# ESP_esquem_tico.net
KiCad netlist of a schematic drawn in EAGLE
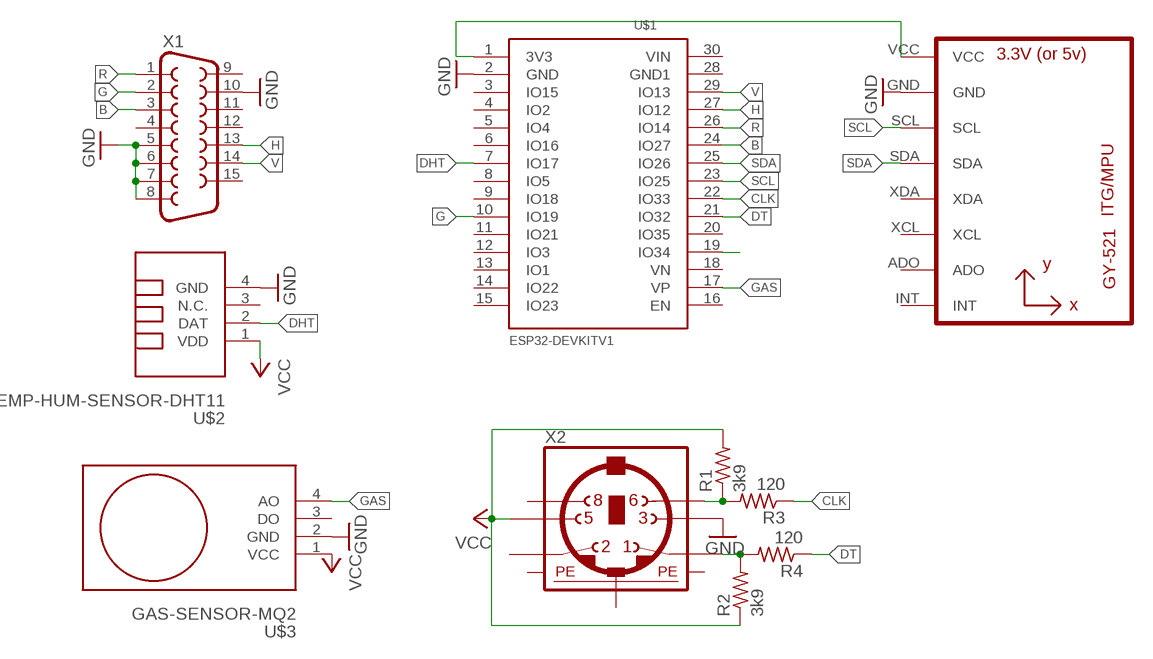
[diagram p0: schematic, sheet 1]

(export (version "E")
  (design (tool "Eeschema 10.0.6"))
  (components
    (comp (ref "R1")
      (value "3k9")
      (footprint "eagle-import:0204_7")
      (libsource (lib "eagle-import") (part "R-US_0204/7"))
    )
    (comp (ref "R2")
      (value "3k9")
      (footprint "eagle-import:0204_7")
      (libsource (lib "eagle-import") (part "R-US_0204/7"))
    )
    (comp (ref "R3")
      (value "120")
      (footprint "eagle-import:0204_7")
      (libsource (lib "eagle-import") (part "R-US_0204/7"))
    )
    (comp (ref "R4")
      (value "120")
      (footprint "eagle-import:0204_7")
      (libsource (lib "eagle-import") (part "R-US_0204/7"))
    )
    (comp (ref "U$1")
      (value "ESP32DEVKITV1")
      (footprint "eagle-import:ESP32-DEVKITV1")
      (libsource (lib "eagle-import") (part "ESP32DEVKITV1"))
    )
    (comp (ref "U$2")
      (value "TEMP-HUM-SENSOR-DHT11")
      (footprint "eagle-import:TEMP-HUM-SENSOR-DHT11")
      (libsource (lib "eagle-import") (part "TEMP-HUM-SENSOR-DHT11"))
    )
    (comp (ref "U$3")
      (value "GAS-SENSOR-MQ2")
      (footprint "eagle-import:GAS-SENSOR-MQ2")
      (libsource (lib "eagle-import") (part "GAS-SENSOR-MQ2"))
    )
    (comp (ref "U1")
      (value "GY-521MPU6050")
      (footprint "eagle-import:GY-521")
      (libsource (lib "eagle-import") (part "GY-521MPU6050"))
    )
    (comp (ref "X1")
      (value "F15HDH")
      (footprint "eagle-import:HDF15H")
      (libsource (lib "eagle-import") (part "F15HDH"))
    )
    (comp (ref "X2")
      (value "MINI_DIN_6")
      (footprint "eagle-import:M_DIN6")
      (libsource (lib "eagle-import") (part "MINI_DIN_6"))
    )
  )
  (nets
    (net (code "1") (name "/PE1") (class "Default")
      (node (ref "X2") (pin "SH1") (pinfunction "PE1_SH1") (pintype "power_in"))
    )
    (net (code "2") (name "/PE2") (class "Default")
      (node (ref "X2") (pin "SH2") (pinfunction "PE2_SH2") (pintype "power_in"))
    )
    (net (code "3") (name "/PE3") (class "Default")
      (node (ref "X2") (pin "SH3") (pinfunction "PE3_SH3") (pintype "power_in"))
    )
    (net (code "4") (name "B") (class "Default")
      (node (ref "U$1") (pin "24") (pinfunction "IO27_24") (pintype "bidirectional"))
      (node (ref "X1") (pin "3") (pinfunction "3_3") (pintype "passive"))
    )
    (net (code "5") (name "CLK") (class "Default")
      (node (ref "R3") (pin "1") (pinfunction "1_1") (pintype "passive"))
      (node (ref "U$1") (pin "22") (pinfunction "IO33_22") (pintype "bidirectional"))
    )
    (net (code "6") (name "DHT") (class "Default")
      (node (ref "U$1") (pin "7") (pinfunction "IO17_7") (pintype "bidirectional"))
      (node (ref "U$2") (pin "2") (pinfunction "DAT_2") (pintype "bidirectional"))
    )
    (net (code "7") (name "DT") (class "Default")
      (node (ref "R4") (pin "1") (pinfunction "1_1") (pintype "passive"))
      (node (ref "U$1") (pin "21") (pinfunction "IO32_21") (pintype "bidirectional"))
    )
    (net (code "8") (name "G") (class "Default")
      (node (ref "U$1") (pin "10") (pinfunction "IO19_10") (pintype "bidirectional"))
      (node (ref "X1") (pin "2") (pinfunction "2_2") (pintype "passive"))
    )
    (net (code "9") (name "GAS") (class "Default")
      (node (ref "U$1") (pin "17") (pinfunction "VP_17") (pintype "bidirectional"))
      (node (ref "U$3") (pin "4") (pinfunction "AO_4") (pintype "output"))
    )
    (net (code "10") (name "GND") (class "Default")
      (node (ref "U$1") (pin "2") (pinfunction "GND_2") (pintype "bidirectional"))
      (node (ref "U$2") (pin "4") (pinfunction "GND_4") (pintype "power_in"))
      (node (ref "U$3") (pin "2") (pinfunction "GND_2") (pintype "power_in"))
      (node (ref "U1") (pin "GND") (pinfunction "GND_GND") (pintype "bidirectional"))
      (node (ref "X1") (pin "10") (pinfunction "10_10") (pintype "passive"))
      (node (ref "X1") (pin "5") (pinfunction "5_5") (pintype "passive"))
      (node (ref "X1") (pin "6") (pinfunction "6_6") (pintype "passive"))
      (node (ref "X1") (pin "7") (pinfunction "7_7") (pintype "passive"))
      (node (ref "X1") (pin "8") (pinfunction "8_8") (pintype "passive"))
      (node (ref "X2") (pin "3") (pinfunction "3_3") (pintype "passive"))
    )
    (net (code "11") (name "H") (class "Default")
      (node (ref "U$1") (pin "27") (pinfunction "IO12_27") (pintype "bidirectional"))
      (node (ref "X1") (pin "13") (pinfunction "13_13") (pintype "passive"))
    )
    (net (code "12") (name "Net-(R1-Pad1)") (class "Default")
      (node (ref "R1") (pin "1") (pinfunction "1_1") (pintype "passive"))
      (node (ref "R3") (pin "2") (pinfunction "2_2") (pintype "passive"))
      (node (ref "X2") (pin "6") (pinfunction "6_6") (pintype "passive"))
    )
    (net (code "13") (name "Net-(R2-Pad2)") (class "Default")
      (node (ref "R2") (pin "2") (pinfunction "2_2") (pintype "passive"))
      (node (ref "R4") (pin "2") (pinfunction "2_2") (pintype "passive"))
      (node (ref "X2") (pin "1") (pinfunction "1_1") (pintype "passive"))
    )
    (net (code "14") (name "Net-(U$1-3V3)") (class "Default")
      (node (ref "U$1") (pin "1") (pinfunction "3V3_1") (pintype "bidirectional"))
      (node (ref "U1") (pin "VCC") (pinfunction "VCC_VCC") (pintype "bidirectional"))
    )
    (net (code "15") (name "R") (class "Default")
      (node (ref "U$1") (pin "26") (pinfunction "IO14_26") (pintype "bidirectional"))
      (node (ref "X1") (pin "1") (pinfunction "1_1") (pintype "passive"))
    )
    (net (code "16") (name "SCL") (class "Default")
      (node (ref "U$1") (pin "23") (pinfunction "IO25_23") (pintype "bidirectional"))
      (node (ref "U1") (pin "SCL") (pinfunction "SCL_SCL") (pintype "bidirectional"))
    )
    (net (code "17") (name "SDA") (class "Default")
      (node (ref "U$1") (pin "25") (pinfunction "IO26_25") (pintype "bidirectional"))
      (node (ref "U1") (pin "SDA") (pinfunction "SDA_SDA") (pintype "bidirectional"))
    )
    (net (code "18") (name "V") (class "Default")
      (node (ref "U$1") (pin "29") (pinfunction "IO13_29") (pintype "bidirectional"))
      (node (ref "X1") (pin "14") (pinfunction "14_14") (pintype "passive"))
    )
    (net (code "19") (name "VCC") (class "Default")
      (node (ref "R1") (pin "2") (pinfunction "2_2") (pintype "passive"))
      (node (ref "R2") (pin "1") (pinfunction "1_1") (pintype "passive"))
      (node (ref "U$2") (pin "1") (pinfunction "VDD_1") (pintype "power_in"))
      (node (ref "U$3") (pin "1") (pinfunction "VCC_1") (pintype "power_in"))
      (node (ref "X2") (pin "5") (pinfunction "5_5") (pintype "passive"))
    )
    (net (code "20") (name "unconnected-(U$1-EN-Pad16)") (class "Default")
      (node (ref "U$1") (pin "16") (pinfunction "EN_16") (pintype "bidirectional"))
    )
    (net (code "21") (name "unconnected-(U$1-GND1-Pad28)") (class "Default")
      (node (ref "U$1") (pin "28") (pinfunction "GND1_28") (pintype "bidirectional"))
    )
    (net (code "22") (name "unconnected-(U$1-IO1-Pad13)") (class "Default")
      (node (ref "U$1") (pin "13") (pinfunction "IO1_13") (pintype "bidirectional"))
    )
    (net (code "23") (name "unconnected-(U$1-IO2-Pad4)") (class "Default")
      (node (ref "U$1") (pin "4") (pinfunction "IO2_4") (pintype "bidirectional"))
    )
    (net (code "24") (name "unconnected-(U$1-IO3-Pad12)") (class "Default")
      (node (ref "U$1") (pin "12") (pinfunction "IO3_12") (pintype "bidirectional"))
    )
    (net (code "25") (name "unconnected-(U$1-IO4-Pad5)") (class "Default")
      (node (ref "U$1") (pin "5") (pinfunction "IO4_5") (pintype "bidirectional"))
    )
    (net (code "26") (name "unconnected-(U$1-IO5-Pad8)") (class "Default")
      (node (ref "U$1") (pin "8") (pinfunction "IO5_8") (pintype "bidirectional"))
    )
    (net (code "27") (name "unconnected-(U$1-IO15-Pad3)") (class "Default")
      (node (ref "U$1") (pin "3") (pinfunction "IO15_3") (pintype "bidirectional"))
    )
    (net (code "28") (name "unconnected-(U$1-IO16-Pad6)") (class "Default")
      (node (ref "U$1") (pin "6") (pinfunction "IO16_6") (pintype "bidirectional"))
    )
    (net (code "29") (name "unconnected-(U$1-IO18-Pad9)") (class "Default")
      (node (ref "U$1") (pin "9") (pinfunction "IO18_9") (pintype "bidirectional"))
    )
    (net (code "30") (name "unconnected-(U$1-IO21-Pad11)") (class "Default")
      (node (ref "U$1") (pin "11") (pinfunction "IO21_11") (pintype "bidirectional"))
    )
    (net (code "31") (name "unconnected-(U$1-IO22-Pad14)") (class "Default")
      (node (ref "U$1") (pin "14") (pinfunction "IO22_14") (pintype "bidirectional"))
    )
    (net (code "32") (name "unconnected-(U$1-IO23-Pad15)") (class "Default")
      (node (ref "U$1") (pin "15") (pinfunction "IO23_15") (pintype "bidirectional"))
    )
    (net (code "33") (name "unconnected-(U$1-IO34-Pad19)") (class "Default")
      (node (ref "U$1") (pin "19") (pinfunction "IO34_19") (pintype "bidirectional"))
    )
    (net (code "34") (name "unconnected-(U$1-IO35-Pad20)") (class "Default")
      (node (ref "U$1") (pin "20") (pinfunction "IO35_20") (pintype "bidirectional"))
    )
    (net (code "35") (name "unconnected-(U$1-VIN-Pad30)") (class "Default")
      (node (ref "U$1") (pin "30") (pinfunction "VIN_30") (pintype "bidirectional"))
    )
    (net (code "36") (name "unconnected-(U$1-VN-Pad18)") (class "Default")
      (node (ref "U$1") (pin "18") (pinfunction "VN_18") (pintype "bidirectional"))
    )
    (net (code "37") (name "unconnected-(U$2-N.C.-Pad3)") (class "Default")
      (node (ref "U$2") (pin "3") (pinfunction "N.C._3") (pintype "passive"))
    )
    (net (code "38") (name "unconnected-(U$3-DO-Pad3)") (class "Default")
      (node (ref "U$3") (pin "3") (pinfunction "DO_3") (pintype "output"))
    )
    (net (code "39") (name "unconnected-(U1-PadADO)") (class "Default")
      (node (ref "U1") (pin "ADO") (pinfunction "ADO_ADO") (pintype "bidirectional"))
    )
    (net (code "40") (name "unconnected-(U1-PadINT)") (class "Default")
      (node (ref "U1") (pin "INT") (pinfunction "INT_INT") (pintype "bidirectional"))
    )
    (net (code "41") (name "unconnected-(U1-PadXCL)") (class "Default")
      (node (ref "U1") (pin "XCL") (pinfunction "XCL_XCL") (pintype "bidirectional"))
    )
    (net (code "42") (name "unconnected-(U1-PadXDA)") (class "Default")
      (node (ref "U1") (pin "XDA") (pinfunction "XDA_XDA") (pintype "bidirectional"))
    )
    (net (code "43") (name "unconnected-(X1-Pad4)") (class "Default")
      (node (ref "X1") (pin "4") (pinfunction "4_4") (pintype "passive"))
    )
    (net (code "44") (name "unconnected-(X1-Pad9)") (class "Default")
      (node (ref "X1") (pin "9") (pinfunction "9_9") (pintype "passive"))
    )
    (net (code "45") (name "unconnected-(X1-Pad11)") (class "Default")
      (node (ref "X1") (pin "11") (pinfunction "11_11") (pintype "passive"))
    )
    (net (code "46") (name "unconnected-(X1-Pad12)") (class "Default")
      (node (ref "X1") (pin "12") (pinfunction "12_12") (pintype "passive"))
    )
    (net (code "47") (name "unconnected-(X1-Pad15)") (class "Default")
      (node (ref "X1") (pin "15") (pinfunction "15_15") (pintype "passive"))
    )
    (net (code "48") (name "unconnected-(X2-Pad2)") (class "Default")
      (node (ref "X2") (pin "2") (pinfunction "2_2") (pintype "passive"))
    )
    (net (code "49") (name "unconnected-(X2-Pad8)") (class "Default")
      (node (ref "X2") (pin "8") (pinfunction "8_8") (pintype "passive"))
    )
  )
)
